# Temperature_Sensor_Rev_4.net
KiCad netlist of a schematic drawn in EAGLE
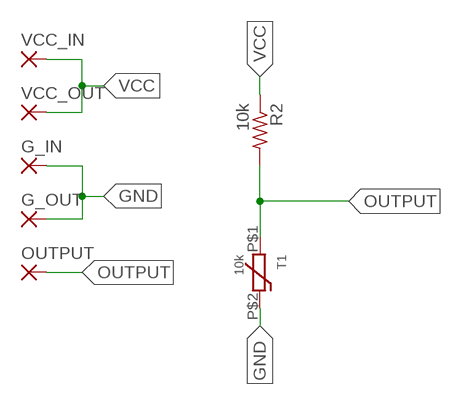
[diagram p0: schematic, sheet 1]

(export (version "E")
  (design (tool "Eeschema 10.0.6"))
  (components
    (comp (ref "G_IN")
      (value "1,6/0,8")
      (footprint "eagle-import:1,6_0,8")
      (libsource (lib "eagle-import") (part "1,6/0,8"))
    )
    (comp (ref "G_OUT")
      (value "1,6/0,8")
      (footprint "eagle-import:1,6_0,8")
      (libsource (lib "eagle-import") (part "1,6/0,8"))
    )
    (comp (ref "OUTPUT")
      (value "1,6/0,8")
      (footprint "eagle-import:1,6_0,8")
      (libsource (lib "eagle-import") (part "1,6/0,8"))
    )
    (comp (ref "R2")
      (value "10k")
      (footprint "eagle-import:R0603")
      (libsource (lib "eagle-import") (part "R-US_R0603"))
    )
    (comp (ref "T1")
      (value "10k")
      (footprint "eagle-import:0603")
      (libsource (lib "eagle-import") (part "THERMISTOR"))
    )
    (comp (ref "VCC_IN")
      (value "1,6/0,8")
      (footprint "eagle-import:1,6_0,8")
      (libsource (lib "eagle-import") (part "1,6/0,8"))
    )
    (comp (ref "VCC_OUT")
      (value "1,6/0,8")
      (footprint "eagle-import:1,6_0,8")
      (libsource (lib "eagle-import") (part "1,6/0,8"))
    )
  )
  (nets
    (net (code "1") (name "GND") (class "Default")
      (node (ref "G_IN") (pin "1") (pinfunction "P_1") (pintype "passive"))
      (node (ref "G_OUT") (pin "1") (pinfunction "P_1") (pintype "passive"))
      (node (ref "T1") (pin "P$2") (pinfunction "P$2_P$2") (pintype "bidirectional"))
    )
    (net (code "2") (name "OUTPUT") (class "Default")
      (node (ref "OUTPUT") (pin "1") (pinfunction "P_1") (pintype "passive"))
      (node (ref "R2") (pin "2") (pinfunction "2_2") (pintype "passive"))
      (node (ref "T1") (pin "P$1") (pinfunction "P$1_P$1") (pintype "bidirectional"))
    )
    (net (code "3") (name "VCC") (class "Default")
      (node (ref "R2") (pin "1") (pinfunction "1_1") (pintype "passive"))
      (node (ref "VCC_IN") (pin "1") (pinfunction "P_1") (pintype "passive"))
      (node (ref "VCC_OUT") (pin "1") (pinfunction "P_1") (pintype "passive"))
    )
  )
)
